# Team18_V1.net
KiCad netlist of a schematic drawn in EAGLE
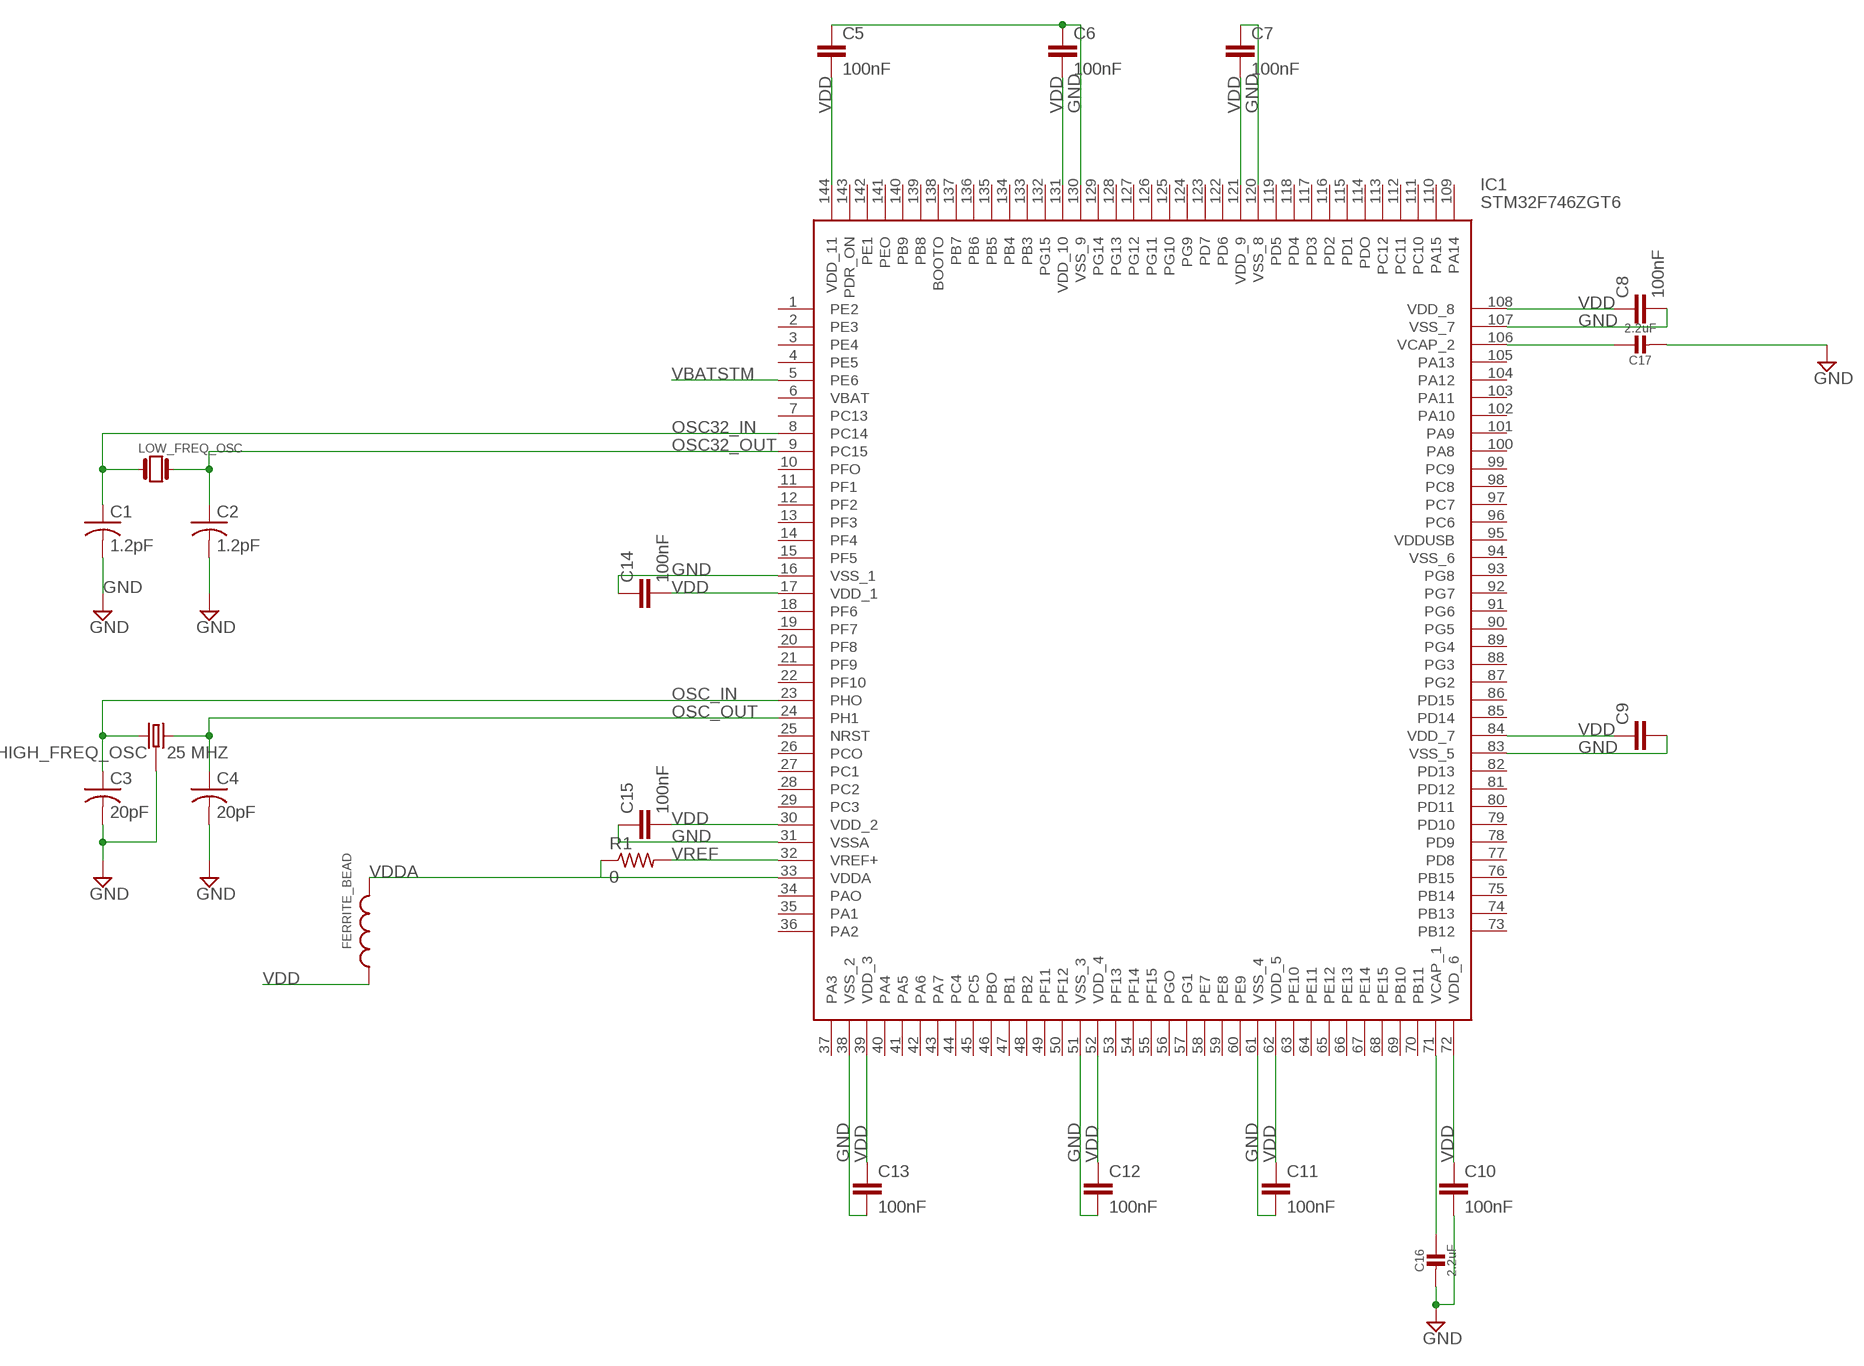
[diagram p0: schematic, sheet 1, part 1 of 2]
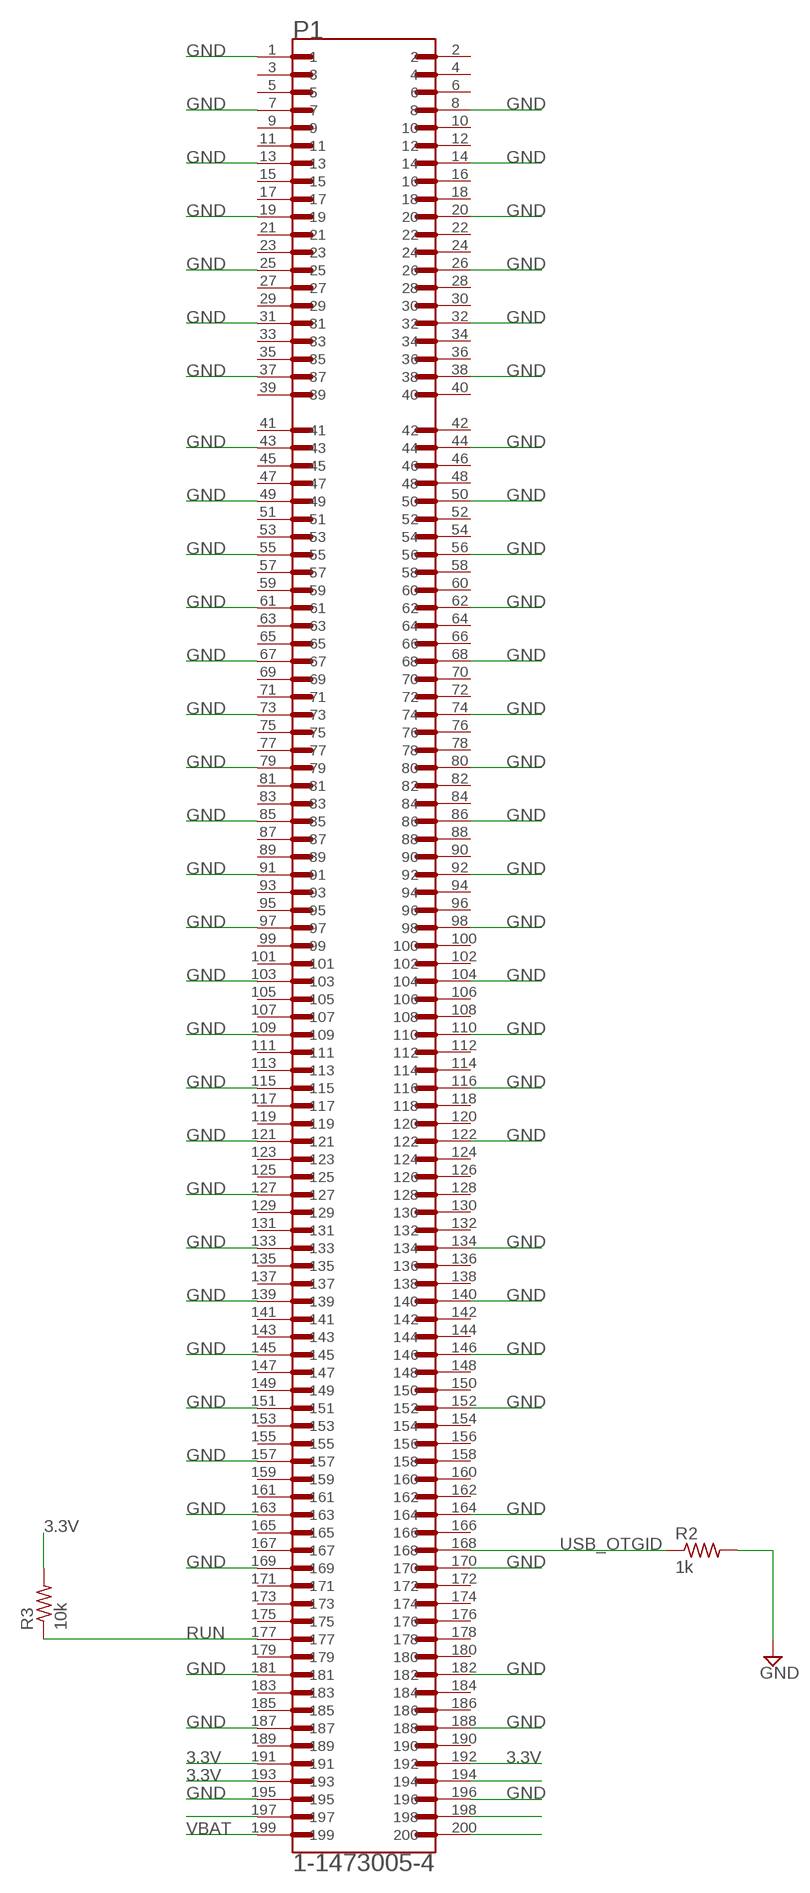
[diagram p1: schematic, sheet 1, part 2 of 2]

(export (version "E")
  (design (tool "Eeschema 10.0.6"))
  (components
    (comp (ref "C1")
      (value "1.2pF")
      (footprint "eagle-import:C0805")
      (libsource (lib "eagle-import") (part "C-USC0805"))
    )
    (comp (ref "C2")
      (value "1.2pF")
      (footprint "eagle-import:C0805")
      (libsource (lib "eagle-import") (part "C-USC0805"))
    )
    (comp (ref "C3")
      (value "20pF")
      (footprint "eagle-import:C0805")
      (libsource (lib "eagle-import") (part "C-USC0805"))
    )
    (comp (ref "C4")
      (value "20pF")
      (footprint "eagle-import:C0805")
      (libsource (lib "eagle-import") (part "C-USC0805"))
    )
    (comp (ref "C5")
      (value "100nF")
      (footprint "eagle-import:C0805")
      (libsource (lib "eagle-import") (part "C-EUC0805"))
    )
    (comp (ref "C6")
      (value "100nF")
      (footprint "eagle-import:C0805")
      (libsource (lib "eagle-import") (part "C-EUC0805"))
    )
    (comp (ref "C7")
      (value "100nF")
      (footprint "eagle-import:C0805")
      (libsource (lib "eagle-import") (part "C-EUC0805"))
    )
    (comp (ref "C8")
      (value "100nF")
      (footprint "eagle-import:C0805")
      (libsource (lib "eagle-import") (part "C-EUC0805"))
    )
    (comp (ref "C9")
      (value "C-EUC0805")
      (footprint "eagle-import:C0805")
      (libsource (lib "eagle-import") (part "C-EUC0805"))
    )
    (comp (ref "C10")
      (value "100nF")
      (footprint "eagle-import:C0805")
      (libsource (lib "eagle-import") (part "C-EUC0805"))
    )
    (comp (ref "C11")
      (value "100nF")
      (footprint "eagle-import:C0805")
      (libsource (lib "eagle-import") (part "C-EUC0805"))
    )
    (comp (ref "C12")
      (value "100nF")
      (footprint "eagle-import:C0805")
      (libsource (lib "eagle-import") (part "C-EUC0805"))
    )
    (comp (ref "C13")
      (value "100nF")
      (footprint "eagle-import:C0805")
      (libsource (lib "eagle-import") (part "C-EUC0805"))
    )
    (comp (ref "C14")
      (value "100nF")
      (footprint "eagle-import:C0805")
      (libsource (lib "eagle-import") (part "C-EUC0805"))
    )
    (comp (ref "C15")
      (value "100nF")
      (footprint "eagle-import:C0805")
      (libsource (lib "eagle-import") (part "C-EUC0805"))
    )
    (comp (ref "C16")
      (value "2.2uF")
      (footprint "eagle-import:0805-NO")
      (libsource (lib "eagle-import") (part "CAP_CERAMIC0805-NOOUTLINE"))
    )
    (comp (ref "C17")
      (value "2.2uF")
      (footprint "eagle-import:0805-NO")
      (libsource (lib "eagle-import") (part "CAP_CERAMIC0805-NOOUTLINE"))
    )
    (comp (ref "FERRITE_BEAD")
      (value "WE-CBA_0805_782853112_HC")
      (footprint "eagle-import:WE-CBA_0805(W=4)")
      (libsource (lib "eagle-import") (part "WE-CBA_0805_HC_782853112"))
    )
    (comp (ref "HIGH_FREQ_OSC")
      (value "25 MHZ")
      (footprint "eagle-import:CRYSTAL-SMD-3.2X2.5MM")
      (libsource (lib "eagle-import") (part "CRYSTAL-26MHZSMD-3.2X2.5"))
    )
    (comp (ref "IC1")
      (value "STM32F746ZGT6")
      (footprint "eagle-import:QFP50P2200X2200X160-144N")
      (fields
        (field (name "MOUSER_PART_NUMBER") "511-STM32F746ZGT6")
        (field (name "RS_PART_NUMBER") "8820290")
      )
      (libsource (lib "eagle-import") (part "STM32F746ZGT6"))
    )
    (comp (ref "LOW_FREQ_OSC")
      (value "GENERIC-CRYSTAL_FC135")
      (footprint "eagle-import:FC135")
      (libsource (lib "eagle-import") (part "GENERIC-CRYSTAL_FC135"))
    )
    (comp (ref "P1")
      (value "1-1473005-4")
      (footprint "eagle-import:TE_1-1473005-4")
      (fields (field (name "MF") "TE Connectivity"))
      (libsource (lib "eagle-import") (part "1-1473005-4"))
    )
    (comp (ref "R1")
      (value "0")
      (footprint "eagle-import:R0805")
      (libsource (lib "eagle-import") (part "R-US_R0805"))
    )
    (comp (ref "R2")
      (value "1k")
      (footprint "eagle-import:R0805")
      (libsource (lib "eagle-import") (part "R-US_R0805"))
    )
    (comp (ref "R3")
      (value "10k")
      (footprint "eagle-import:R0805")
      (libsource (lib "eagle-import") (part "R-US_R0805"))
    )
  )
  (nets
    (net (code "1") (name "/3.3V") (class "Default")
      (node (ref "P1") (pin "191") (pinfunction "191_191") (pintype "passive"))
      (node (ref "P1") (pin "192") (pinfunction "192_192") (pintype "passive"))
      (node (ref "P1") (pin "193") (pinfunction "193_193") (pintype "passive"))
      (node (ref "P1") (pin "194") (pinfunction "194_194") (pintype "passive"))
      (node (ref "R3") (pin "2") (pinfunction "2_2") (pintype "passive"))
    )
    (net (code "2") (name "/OSC32_IN") (class "Default")
      (node (ref "C1") (pin "1") (pinfunction "1_1") (pintype "passive"))
      (node (ref "IC1") (pin "8") (pinfunction "PC14_8") (pintype "bidirectional"))
      (node (ref "LOW_FREQ_OSC") (pin "X1") (pinfunction "1_X1") (pintype "passive"))
    )
    (net (code "3") (name "/OSC32_OUT") (class "Default")
      (node (ref "C2") (pin "1") (pinfunction "1_1") (pintype "passive"))
      (node (ref "IC1") (pin "9") (pinfunction "PC15_9") (pintype "bidirectional"))
      (node (ref "LOW_FREQ_OSC") (pin "X2") (pinfunction "2_X2") (pintype "passive"))
    )
    (net (code "4") (name "/OSC_IN") (class "Default")
      (node (ref "C3") (pin "1") (pinfunction "1_1") (pintype "passive"))
      (node (ref "HIGH_FREQ_OSC") (pin "1") (pinfunction "1_1") (pintype "passive"))
      (node (ref "IC1") (pin "23") (pinfunction "PHO_23") (pintype "bidirectional"))
    )
    (net (code "5") (name "/OSC_OUT") (class "Default")
      (node (ref "C4") (pin "1") (pinfunction "1_1") (pintype "passive"))
      (node (ref "HIGH_FREQ_OSC") (pin "3") (pinfunction "2_3") (pintype "passive"))
      (node (ref "IC1") (pin "24") (pinfunction "PH1_24") (pintype "bidirectional"))
    )
    (net (code "6") (name "/RUN") (class "Default")
      (node (ref "P1") (pin "177") (pinfunction "177_177") (pintype "passive"))
      (node (ref "R3") (pin "1") (pinfunction "1_1") (pintype "passive"))
    )
    (net (code "7") (name "/USB_OTGID") (class "Default")
      (node (ref "P1") (pin "168") (pinfunction "168_168") (pintype "passive"))
      (node (ref "R2") (pin "1") (pinfunction "1_1") (pintype "passive"))
    )
    (net (code "8") (name "/VBAT") (class "Default")
      (node (ref "P1") (pin "197") (pinfunction "197_197") (pintype "passive"))
      (node (ref "P1") (pin "198") (pinfunction "198_198") (pintype "passive"))
      (node (ref "P1") (pin "199") (pinfunction "199_199") (pintype "passive"))
      (node (ref "P1") (pin "200") (pinfunction "200_200") (pintype "passive"))
    )
    (net (code "9") (name "/VBATSTM") (class "Default")
      (node (ref "IC1") (pin "5") (pinfunction "PE6_5") (pintype "bidirectional"))
    )
    (net (code "10") (name "/VDD") (class "Default")
      (node (ref "C10") (pin "1") (pinfunction "1_1") (pintype "passive"))
      (node (ref "C11") (pin "1") (pinfunction "1_1") (pintype "passive"))
      (node (ref "C12") (pin "1") (pinfunction "1_1") (pintype "passive"))
      (node (ref "C13") (pin "1") (pinfunction "1_1") (pintype "passive"))
      (node (ref "C14") (pin "2") (pinfunction "2_2") (pintype "passive"))
      (node (ref "C15") (pin "2") (pinfunction "2_2") (pintype "passive"))
      (node (ref "C5") (pin "2") (pinfunction "2_2") (pintype "passive"))
      (node (ref "C6") (pin "2") (pinfunction "2_2") (pintype "passive"))
      (node (ref "C7") (pin "2") (pinfunction "2_2") (pintype "passive"))
      (node (ref "C8") (pin "1") (pinfunction "1_1") (pintype "passive"))
      (node (ref "C9") (pin "1") (pinfunction "1_1") (pintype "passive"))
      (node (ref "FERRITE_BEAD") (pin "1") (pinfunction "1_1") (pintype "passive"))
      (node (ref "IC1") (pin "108") (pinfunction "VDD_8_108") (pintype "power_in"))
      (node (ref "IC1") (pin "121") (pinfunction "VDD_9_121") (pintype "power_in"))
      (node (ref "IC1") (pin "131") (pinfunction "VDD_10_131") (pintype "power_in"))
      (node (ref "IC1") (pin "144") (pinfunction "VDD_11_144") (pintype "power_in"))
      (node (ref "IC1") (pin "17") (pinfunction "VDD_1_17") (pintype "power_in"))
      (node (ref "IC1") (pin "30") (pinfunction "VDD_2_30") (pintype "power_in"))
      (node (ref "IC1") (pin "39") (pinfunction "VDD_3_39") (pintype "power_in"))
      (node (ref "IC1") (pin "52") (pinfunction "VDD_4_52") (pintype "power_in"))
      (node (ref "IC1") (pin "62") (pinfunction "VDD_5_62") (pintype "power_in"))
      (node (ref "IC1") (pin "72") (pinfunction "VDD_6_72") (pintype "power_in"))
      (node (ref "IC1") (pin "84") (pinfunction "VDD_7_84") (pintype "power_in"))
    )
    (net (code "11") (name "/VDDA") (class "Default")
      (node (ref "FERRITE_BEAD") (pin "2") (pinfunction "2_2") (pintype "passive"))
      (node (ref "IC1") (pin "33") (pinfunction "VDDA_33") (pintype "power_in"))
      (node (ref "R1") (pin "1") (pinfunction "1_1") (pintype "passive"))
    )
    (net (code "12") (name "/VDDUSB") (class "Default")
      (node (ref "IC1") (pin "95") (pinfunction "VDDUSB_95") (pintype "power_in"))
    )
    (net (code "13") (name "/VREF") (class "Default")
      (node (ref "IC1") (pin "32") (pinfunction "VREF+_32") (pintype "input"))
      (node (ref "R1") (pin "2") (pinfunction "2_2") (pintype "passive"))
    )
    (net (code "14") (name "/VSS_6") (class "Default")
      (node (ref "IC1") (pin "94") (pinfunction "VSS_6_94") (pintype "power_in"))
    )
    (net (code "15") (name "GND") (class "Default")
      (node (ref "C1") (pin "2") (pinfunction "2_2") (pintype "passive"))
      (node (ref "C10") (pin "2") (pinfunction "2_2") (pintype "passive"))
      (node (ref "C11") (pin "2") (pinfunction "2_2") (pintype "passive"))
      (node (ref "C12") (pin "2") (pinfunction "2_2") (pintype "passive"))
      (node (ref "C13") (pin "2") (pinfunction "2_2") (pintype "passive"))
      (node (ref "C14") (pin "1") (pinfunction "1_1") (pintype "passive"))
      (node (ref "C15") (pin "1") (pinfunction "1_1") (pintype "passive"))
      (node (ref "C16") (pin "2") (pinfunction "2_2") (pintype "passive"))
      (node (ref "C17") (pin "2") (pinfunction "2_2") (pintype "passive"))
      (node (ref "C2") (pin "2") (pinfunction "2_2") (pintype "passive"))
      (node (ref "C3") (pin "2") (pinfunction "2_2") (pintype "passive"))
      (node (ref "C4") (pin "2") (pinfunction "2_2") (pintype "passive"))
      (node (ref "C5") (pin "1") (pinfunction "1_1") (pintype "passive"))
      (node (ref "C6") (pin "1") (pinfunction "1_1") (pintype "passive"))
      (node (ref "C7") (pin "1") (pinfunction "1_1") (pintype "passive"))
      (node (ref "C8") (pin "2") (pinfunction "2_2") (pintype "passive"))
      (node (ref "C9") (pin "2") (pinfunction "2_2") (pintype "passive"))
      (node (ref "HIGH_FREQ_OSC") (pin "2") (pinfunction "3_2") (pintype "passive"))
      (node (ref "HIGH_FREQ_OSC") (pin "4") (pinfunction "3_4") (pintype "passive"))
      (node (ref "IC1") (pin "107") (pinfunction "VSS_7_107") (pintype "power_in"))
      (node (ref "IC1") (pin "120") (pinfunction "VSS_8_120") (pintype "power_in"))
      (node (ref "IC1") (pin "130") (pinfunction "VSS_9_130") (pintype "power_in"))
      (node (ref "IC1") (pin "16") (pinfunction "VSS_1_16") (pintype "power_in"))
      (node (ref "IC1") (pin "31") (pinfunction "VSSA_31") (pintype "power_in"))
      (node (ref "IC1") (pin "38") (pinfunction "VSS_2_38") (pintype "power_in"))
      (node (ref "IC1") (pin "51") (pinfunction "VSS_3_51") (pintype "power_in"))
      (node (ref "IC1") (pin "61") (pinfunction "VSS_4_61") (pintype "power_in"))
      (node (ref "IC1") (pin "83") (pinfunction "VSS_5_83") (pintype "power_in"))
      (node (ref "P1") (pin "1") (pinfunction "1_1") (pintype "passive"))
      (node (ref "P1") (pin "103") (pinfunction "103_103") (pintype "passive"))
      (node (ref "P1") (pin "104") (pinfunction "104_104") (pintype "passive"))
      (node (ref "P1") (pin "109") (pinfunction "109_109") (pintype "passive"))
      (node (ref "P1") (pin "110") (pinfunction "110_110") (pintype "passive"))
      (node (ref "P1") (pin "115") (pinfunction "115_115") (pintype "passive"))
      (node (ref "P1") (pin "116") (pinfunction "116_116") (pintype "passive"))
      (node (ref "P1") (pin "121") (pinfunction "121_121") (pintype "passive"))
      (node (ref "P1") (pin "122") (pinfunction "122_122") (pintype "passive"))
      (node (ref "P1") (pin "127") (pinfunction "127_127") (pintype "passive"))
      (node (ref "P1") (pin "13") (pinfunction "13_13") (pintype "passive"))
      (node (ref "P1") (pin "133") (pinfunction "133_133") (pintype "passive"))
      (node (ref "P1") (pin "134") (pinfunction "134_134") (pintype "passive"))
      (node (ref "P1") (pin "139") (pinfunction "139_139") (pintype "passive"))
      (node (ref "P1") (pin "14") (pinfunction "14_14") (pintype "passive"))
      (node (ref "P1") (pin "140") (pinfunction "140_140") (pintype "passive"))
      (node (ref "P1") (pin "145") (pinfunction "145_145") (pintype "passive"))
      (node (ref "P1") (pin "146") (pinfunction "146_146") (pintype "passive"))
      (node (ref "P1") (pin "151") (pinfunction "151_151") (pintype "passive"))
      (node (ref "P1") (pin "152") (pinfunction "152_152") (pintype "passive"))
      (node (ref "P1") (pin "157") (pinfunction "157_157") (pintype "passive"))
      (node (ref "P1") (pin "163") (pinfunction "163_163") (pintype "passive"))
      (node (ref "P1") (pin "164") (pinfunction "164_164") (pintype "passive"))
      (node (ref "P1") (pin "169") (pinfunction "169_169") (pintype "passive"))
      (node (ref "P1") (pin "170") (pinfunction "170_170") (pintype "passive"))
      (node (ref "P1") (pin "181") (pinfunction "181_181") (pintype "passive"))
      (node (ref "P1") (pin "182") (pinfunction "182_182") (pintype "passive"))
      (node (ref "P1") (pin "187") (pinfunction "187_187") (pintype "passive"))
      (node (ref "P1") (pin "188") (pinfunction "188_188") (pintype "passive"))
      (node (ref "P1") (pin "19") (pinfunction "19_19") (pintype "passive"))
      (node (ref "P1") (pin "195") (pinfunction "195_195") (pintype "passive"))
      (node (ref "P1") (pin "196") (pinfunction "196_196") (pintype "passive"))
      (node (ref "P1") (pin "20") (pinfunction "20_20") (pintype "passive"))
      (node (ref "P1") (pin "25") (pinfunction "25_25") (pintype "passive"))
      (node (ref "P1") (pin "26") (pinfunction "26_26") (pintype "passive"))
      (node (ref "P1") (pin "31") (pinfunction "31_31") (pintype "passive"))
      (node (ref "P1") (pin "32") (pinfunction "32_32") (pintype "passive"))
      (node (ref "P1") (pin "37") (pinfunction "37_37") (pintype "passive"))
      (node (ref "P1") (pin "38") (pinfunction "38_38") (pintype "passive"))
      (node (ref "P1") (pin "43") (pinfunction "43_43") (pintype "passive"))
      (node (ref "P1") (pin "44") (pinfunction "44_44") (pintype "passive"))
      (node (ref "P1") (pin "49") (pinfunction "49_49") (pintype "passive"))
      (node (ref "P1") (pin "50") (pinfunction "50_50") (pintype "passive"))
      (node (ref "P1") (pin "55") (pinfunction "55_55") (pintype "passive"))
      (node (ref "P1") (pin "56") (pinfunction "56_56") (pintype "passive"))
      (node (ref "P1") (pin "61") (pinfunction "61_61") (pintype "passive"))
      (node (ref "P1") (pin "62") (pinfunction "62_62") (pintype "passive"))
      (node (ref "P1") (pin "67") (pinfunction "67_67") (pintype "passive"))
      (node (ref "P1") (pin "68") (pinfunction "68_68") (pintype "passive"))
      (node (ref "P1") (pin "7") (pinfunction "7_7") (pintype "passive"))
      (node (ref "P1") (pin "73") (pinfunction "73_73") (pintype "passive"))
      (node (ref "P1") (pin "74") (pinfunction "74_74") (pintype "passive"))
      (node (ref "P1") (pin "79") (pinfunction "79_79") (pintype "passive"))
      (node (ref "P1") (pin "8") (pinfunction "8_8") (pintype "passive"))
      (node (ref "P1") (pin "80") (pinfunction "80_80") (pintype "passive"))
      (node (ref "P1") (pin "85") (pinfunction "85_85") (pintype "passive"))
      (node (ref "P1") (pin "86") (pinfunction "86_86") (pintype "passive"))
      (node (ref "P1") (pin "91") (pinfunction "91_91") (pintype "passive"))
      (node (ref "P1") (pin "92") (pinfunction "92_92") (pintype "passive"))
      (node (ref "P1") (pin "97") (pinfunction "97_97") (pintype "passive"))
      (node (ref "P1") (pin "98") (pinfunction "98_98") (pintype "passive"))
      (node (ref "R2") (pin "2") (pinfunction "2_2") (pintype "passive"))
    )
    (net (code "16") (name "Net-(IC1-VCAP_1)") (class "Default")
      (node (ref "C16") (pin "1") (pinfunction "1_1") (pintype "passive"))
      (node (ref "IC1") (pin "71") (pinfunction "VCAP_1_71") (pintype "bidirectional"))
    )
    (net (code "17") (name "Net-(IC1-VCAP_2)") (class "Default")
      (node (ref "C17") (pin "1") (pinfunction "1_1") (pintype "passive"))
      (node (ref "IC1") (pin "106") (pinfunction "VCAP_2_106") (pintype "bidirectional"))
    )
    (net (code "18") (name "unconnected-(IC1-BOOTO-Pad138)") (class "Default")
      (node (ref "IC1") (pin "138") (pinfunction "BOOTO_138") (pintype "bidirectional"))
    )
    (net (code "19") (name "unconnected-(IC1-NRST-Pad25)") (class "Default")
      (node (ref "IC1") (pin "25") (pinfunction "NRST_25") (pintype "input"))
    )
    (net (code "20") (name "unconnected-(IC1-PA1-Pad35)") (class "Default")
      (node (ref "IC1") (pin "35") (pinfunction "PA1_35") (pintype "bidirectional"))
    )
    (net (code "21") (name "unconnected-(IC1-PA2-Pad36)") (class "Default")
      (node (ref "IC1") (pin "36") (pinfunction "PA2_36") (pintype "bidirectional"))
    )
    (net (code "22") (name "unconnected-(IC1-PA3-Pad37)") (class "Default")
      (node (ref "IC1") (pin "37") (pinfunction "PA3_37") (pintype "bidirectional"))
    )
    (net (code "23") (name "unconnected-(IC1-PA4-Pad40)") (class "Default")
      (node (ref "IC1") (pin "40") (pinfunction "PA4_40") (pintype "bidirectional"))
    )
    (net (code "24") (name "unconnected-(IC1-PA5-Pad41)") (class "Default")
      (node (ref "IC1") (pin "41") (pinfunction "PA5_41") (pintype "bidirectional"))
    )
    (net (code "25") (name "unconnected-(IC1-PA6-Pad42)") (class "Default")
      (node (ref "IC1") (pin "42") (pinfunction "PA6_42") (pintype "bidirectional"))
    )
    (net (code "26") (name "unconnected-(IC1-PA7-Pad43)") (class "Default")
      (node (ref "IC1") (pin "43") (pinfunction "PA7_43") (pintype "bidirectional"))
    )
    (net (code "27") (name "unconnected-(IC1-PA8-Pad100)") (class "Default")
      (node (ref "IC1") (pin "100") (pinfunction "PA8_100") (pintype "bidirectional"))
    )
    (net (code "28") (name "unconnected-(IC1-PA9-Pad101)") (class "Default")
      (node (ref "IC1") (pin "101") (pinfunction "PA9_101") (pintype "bidirectional"))
    )
    (net (code "29") (name "unconnected-(IC1-PA10-Pad102)") (class "Default")
      (node (ref "IC1") (pin "102") (pinfunction "PA10_102") (pintype "bidirectional"))
    )
    (net (code "30") (name "unconnected-(IC1-PA11-Pad103)") (class "Default")
      (node (ref "IC1") (pin "103") (pinfunction "PA11_103") (pintype "bidirectional"))
    )
    (net (code "31") (name "unconnected-(IC1-PA12-Pad104)") (class "Default")
      (node (ref "IC1") (pin "104") (pinfunction "PA12_104") (pintype "bidirectional"))
    )
    (net (code "32") (name "unconnected-(IC1-PA13-Pad105)") (class "Default")
      (node (ref "IC1") (pin "105") (pinfunction "PA13_105") (pintype "bidirectional"))
    )
    (net (code "33") (name "unconnected-(IC1-PA14-Pad109)") (class "Default")
      (node (ref "IC1") (pin "109") (pinfunction "PA14_109") (pintype "bidirectional"))
    )
    (net (code "34") (name "unconnected-(IC1-PA15-Pad110)") (class "Default")
      (node (ref "IC1") (pin "110") (pinfunction "PA15_110") (pintype "bidirectional"))
    )
    (net (code "35") (name "unconnected-(IC1-PAO-Pad34)") (class "Default")
      (node (ref "IC1") (pin "34") (pinfunction "PAO_34") (pintype "bidirectional"))
    )
    (net (code "36") (name "unconnected-(IC1-PB1-Pad47)") (class "Default")
      (node (ref "IC1") (pin "47") (pinfunction "PB1_47") (pintype "bidirectional"))
    )
    (net (code "37") (name "unconnected-(IC1-PB2-Pad48)") (class "Default")
      (node (ref "IC1") (pin "48") (pinfunction "PB2_48") (pintype "bidirectional"))
    )
    (net (code "38") (name "unconnected-(IC1-PB3-Pad133)") (class "Default")
      (node (ref "IC1") (pin "133") (pinfunction "PB3_133") (pintype "bidirectional"))
    )
    (net (code "39") (name "unconnected-(IC1-PB4-Pad134)") (class "Default")
      (node (ref "IC1") (pin "134") (pinfunction "PB4_134") (pintype "bidirectional"))
    )
    (net (code "40") (name "unconnected-(IC1-PB5-Pad135)") (class "Default")
      (node (ref "IC1") (pin "135") (pinfunction "PB5_135") (pintype "bidirectional"))
    )
    (net (code "41") (name "unconnected-(IC1-PB6-Pad136)") (class "Default")
      (node (ref "IC1") (pin "136") (pinfunction "PB6_136") (pintype "bidirectional"))
    )
    (net (code "42") (name "unconnected-(IC1-PB7-Pad137)") (class "Default")
      (node (ref "IC1") (pin "137") (pinfunction "PB7_137") (pintype "bidirectional"))
    )
    (net (code "43") (name "unconnected-(IC1-PB8-Pad139)") (class "Default")
      (node (ref "IC1") (pin "139") (pinfunction "PB8_139") (pintype "bidirectional"))
    )
    (net (code "44") (name "unconnected-(IC1-PB9-Pad140)") (class "Default")
      (node (ref "IC1") (pin "140") (pinfunction "PB9_140") (pintype "bidirectional"))
    )
    (net (code "45") (name "unconnected-(IC1-PB10-Pad69)") (class "Default")
      (node (ref "IC1") (pin "69") (pinfunction "PB10_69") (pintype "bidirectional"))
    )
    (net (code "46") (name "unconnected-(IC1-PB11-Pad70)") (class "Default")
      (node (ref "IC1") (pin "70") (pinfunction "PB11_70") (pintype "bidirectional"))
    )
    (net (code "47") (name "unconnected-(IC1-PB12-Pad73)") (class "Default")
      (node (ref "IC1") (pin "73") (pinfunction "PB12_73") (pintype "bidirectional"))
    )
    (net (code "48") (name "unconnected-(IC1-PB13-Pad74)") (class "Default")
      (node (ref "IC1") (pin "74") (pinfunction "PB13_74") (pintype "bidirectional"))
    )
    (net (code "49") (name "unconnected-(IC1-PB14-Pad75)") (class "Default")
      (node (ref "IC1") (pin "75") (pinfunction "PB14_75") (pintype "bidirectional"))
    )
    (net (code "50") (name "unconnected-(IC1-PB15-Pad76)") (class "Default")
      (node (ref "IC1") (pin "76") (pinfunction "PB15_76") (pintype "bidirectional"))
    )
    (net (code "51") (name "unconnected-(IC1-PBO-Pad46)") (class "Default")
      (node (ref "IC1") (pin "46") (pinfunction "PBO_46") (pintype "bidirectional"))
    )
    (net (code "52") (name "unconnected-(IC1-PC1-Pad27)") (class "Default")
      (node (ref "IC1") (pin "27") (pinfunction "PC1_27") (pintype "bidirectional"))
    )
    (net (code "53") (name "unconnected-(IC1-PC2-Pad28)") (class "Default")
      (node (ref "IC1") (pin "28") (pinfunction "PC2_28") (pintype "bidirectional"))
    )
    (net (code "54") (name "unconnected-(IC1-PC3-Pad29)") (class "Default")
      (node (ref "IC1") (pin "29") (pinfunction "PC3_29") (pintype "bidirectional"))
    )
    (net (code "55") (name "unconnected-(IC1-PC4-Pad44)") (class "Default")
      (node (ref "IC1") (pin "44") (pinfunction "PC4_44") (pintype "bidirectional"))
    )
    (net (code "56") (name "unconnected-(IC1-PC5-Pad45)") (class "Default")
      (node (ref "IC1") (pin "45") (pinfunction "PC5_45") (pintype "bidirectional"))
    )
    (net (code "57") (name "unconnected-(IC1-PC6-Pad96)") (class "Default")
      (node (ref "IC1") (pin "96") (pinfunction "PC6_96") (pintype "bidirectional"))
    )
    (net (code "58") (name "unconnected-(IC1-PC7-Pad97)") (class "Default")
      (node (ref "IC1") (pin "97") (pinfunction "PC7_97") (pintype "bidirectional"))
    )
    (net (code "59") (name "unconnected-(IC1-PC8-Pad98)") (class "Default")
      (node (ref "IC1") (pin "98") (pinfunction "PC8_98") (pintype "bidirectional"))
    )
    (net (code "60") (name "unconnected-(IC1-PC9-Pad99)") (class "Default")
      (node (ref "IC1") (pin "99") (pinfunction "PC9_99") (pintype "bidirectional"))
    )
    (net (code "61") (name "unconnected-(IC1-PC10-Pad111)") (class "Default")
      (node (ref "IC1") (pin "111") (pinfunction "PC10_111") (pintype "bidirectional"))
    )
    (net (code "62") (name "unconnected-(IC1-PC11-Pad112)") (class "Default")
      (node (ref "IC1") (pin "112") (pinfunction "PC11_112") (pintype "bidirectional"))
    )
    (net (code "63") (name "unconnected-(IC1-PC12-Pad113)") (class "Default")
      (node (ref "IC1") (pin "113") (pinfunction "PC12_113") (pintype "bidirectional"))
    )
    (net (code "64") (name "unconnected-(IC1-PC13-Pad7)") (class "Default")
      (node (ref "IC1") (pin "7") (pinfunction "PC13_7") (pintype "bidirectional"))
    )
    (net (code "65") (name "unconnected-(IC1-PCO-Pad26)") (class "Default")
      (node (ref "IC1") (pin "26") (pinfunction "PCO_26") (pintype "bidirectional"))
    )
    (net (code "66") (name "unconnected-(IC1-PD1-Pad115)") (class "Default")
      (node (ref "IC1") (pin "115") (pinfunction "PD1_115") (pintype "bidirectional"))
    )
    (net (code "67") (name "unconnected-(IC1-PD2-Pad116)") (class "Default")
      (node (ref "IC1") (pin "116") (pinfunction "PD2_116") (pintype "bidirectional"))
    )
    (net (code "68") (name "unconnected-(IC1-PD3-Pad117)") (class "Default")
      (node (ref "IC1") (pin "117") (pinfunction "PD3_117") (pintype "bidirectional"))
    )
    (net (code "69") (name "unconnected-(IC1-PD4-Pad118)") (class "Default")
      (node (ref "IC1") (pin "118") (pinfunction "PD4_118") (pintype "bidirectional"))
    )
    (net (code "70") (name "unconnected-(IC1-PD5-Pad119)") (class "Default")
      (node (ref "IC1") (pin "119") (pinfunction "PD5_119") (pintype "bidirectional"))
    )
    (net (code "71") (name "unconnected-(IC1-PD6-Pad122)") (class "Default")
      (node (ref "IC1") (pin "122") (pinfunction "PD6_122") (pintype "bidirectional"))
    )
    (net (code "72") (name "unconnected-(IC1-PD7-Pad123)") (class "Default")
      (node (ref "IC1") (pin "123") (pinfunction "PD7_123") (pintype "bidirectional"))
    )
    (net (code "73") (name "unconnected-(IC1-PD8-Pad77)") (class "Default")
      (node (ref "IC1") (pin "77") (pinfunction "PD8_77") (pintype "bidirectional"))
    )
    (net (code "74") (name "unconnected-(IC1-PD9-Pad78)") (class "Default")
      (node (ref "IC1") (pin "78") (pinfunction "PD9_78") (pintype "bidirectional"))
    )
    (net (code "75") (name "unconnected-(IC1-PD10-Pad79)") (class "Default")
      (node (ref "IC1") (pin "79") (pinfunction "PD10_79") (pintype "bidirectional"))
    )
    (net (code "76") (name "unconnected-(IC1-PD11-Pad80)") (class "Default")
      (node (ref "IC1") (pin "80") (pinfunction "PD11_80") (pintype "bidirectional"))
    )
    (net (code "77") (name "unconnected-(IC1-PD12-Pad81)") (class "Default")
      (node (ref "IC1") (pin "81") (pinfunction "PD12_81") (pintype "bidirectional"))
    )
    (net (code "78") (name "unconnected-(IC1-PD13-Pad82)") (class "Default")
      (node (ref "IC1") (pin "82") (pinfunction "PD13_82") (pintype "bidirectional"))
    )
    (net (code "79") (name "unconnected-(IC1-PD14-Pad85)") (class "Default")
      (node (ref "IC1") (pin "85") (pinfunction "PD14_85") (pintype "bidirectional"))
    )
    (net (code "80") (name "unconnected-(IC1-PD15-Pad86)") (class "Default")
      (node (ref "IC1") (pin "86") (pinfunction "PD15_86") (pintype "bidirectional"))
    )
    (net (code "81") (name "unconnected-(IC1-PDO-Pad114)") (class "Default")
      (node (ref "IC1") (pin "114") (pinfunction "PDO_114") (pintype "bidirectional"))
    )
    (net (code "82") (name "unconnected-(IC1-PDR_ON-Pad143)") (class "Default")
      (node (ref "IC1") (pin "143") (pinfunction "PDR_ON_143") (pintype "bidirectional"))
    )
    (net (code "83") (name "unconnected-(IC1-PE1-Pad142)") (class "Default")
      (node (ref "IC1") (pin "142") (pinfunction "PE1_142") (pintype "bidirectional"))
    )
    (net (code "84") (name "unconnected-(IC1-PE2-Pad1)") (class "Default")
      (node (ref "IC1") (pin "1") (pinfunction "PE2_1") (pintype "bidirectional"))
    )
    (net (code "85") (name "unconnected-(IC1-PE3-Pad2)") (class "Default")
      (node (ref "IC1") (pin "2") (pinfunction "PE3_2") (pintype "bidirectional"))
    )
    (net (code "86") (name "unconnected-(IC1-PE4-Pad3)") (class "Default")
      (node (ref "IC1") (pin "3") (pinfunction "PE4_3") (pintype "bidirectional"))
    )
    (net (code "87") (name "unconnected-(IC1-PE5-Pad4)") (class "Default")
      (node (ref "IC1") (pin "4") (pinfunction "PE5_4") (pintype "bidirectional"))
    )
    (net (code "88") (name "unconnected-(IC1-PE7-Pad58)") (class "Default")
      (node (ref "IC1") (pin "58") (pinfunction "PE7_58") (pintype "bidirectional"))
    )
    (net (code "89") (name "unconnected-(IC1-PE8-Pad59)") (class "Default")
      (node (ref "IC1") (pin "59") (pinfunction "PE8_59") (pintype "bidirectional"))
    )
    (net (code "90") (name "unconnected-(IC1-PE9-Pad60)") (class "Default")
      (node (ref "IC1") (pin "60") (pinfunction "PE9_60") (pintype "bidirectional"))
    )
    (net (code "91") (name "unconnected-(IC1-PE10-Pad63)") (class "Default")
      (node (ref "IC1") (pin "63") (pinfunction "PE10_63") (pintype "bidirectional"))
    )
    (net (code "92") (name "unconnected-(IC1-PE11-Pad64)") (class "Default")
      (node (ref "IC1") (pin "64") (pinfunction "PE11_64") (pintype "bidirectional"))
    )
    (net (code "93") (name "unconnected-(IC1-PE12-Pad65)") (class "Default")
      (node (ref "IC1") (pin "65") (pinfunction "PE12_65") (pintype "bidirectional"))
    )
    (net (code "94") (name "unconnected-(IC1-PE13-Pad66)") (class "Default")
      (node (ref "IC1") (pin "66") (pinfunction "PE13_66") (pintype "bidirectional"))
    )
    (net (code "95") (name "unconnected-(IC1-PE14-Pad67)") (class "Default")
      (node (ref "IC1") (pin "67") (pinfunction "PE14_67") (pintype "bidirectional"))
    )
    (net (code "96") (name "unconnected-(IC1-PE15-Pad68)") (class "Default")
      (node (ref "IC1") (pin "68") (pinfunction "PE15_68") (pintype "bidirectional"))
    )
    (net (code "97") (name "unconnected-(IC1-PEO-Pad141)") (class "Default")
      (node (ref "IC1") (pin "141") (pinfunction "PEO_141") (pintype "bidirectional"))
    )
    (net (code "98") (name "unconnected-(IC1-PF1-Pad11)") (class "Default")
      (node (ref "IC1") (pin "11") (pinfunction "PF1_11") (pintype "bidirectional"))
    )
    (net (code "99") (name "unconnected-(IC1-PF2-Pad12)") (class "Default")
      (node (ref "IC1") (pin "12") (pinfunction "PF2_12") (pintype "bidirectional"))
    )
    (net (code "100") (name "unconnected-(IC1-PF3-Pad13)") (class "Default")
      (node (ref "IC1") (pin "13") (pinfunction "PF3_13") (pintype "bidirectional"))
    )
    (net (code "101") (name "unconnected-(IC1-PF4-Pad14)") (class "Default")
      (node (ref "IC1") (pin "14") (pinfunction "PF4_14") (pintype "bidirectional"))
    )
    (net (code "102") (name "unconnected-(IC1-PF5-Pad15)") (class "Default")
      (node (ref "IC1") (pin "15") (pinfunction "PF5_15") (pintype "bidirectional"))
    )
    (net (code "103") (name "unconnected-(IC1-PF6-Pad18)") (class "Default")
      (node (ref "IC1") (pin "18") (pinfunction "PF6_18") (pintype "bidirectional"))
    )
    (net (code "104") (name "unconnected-(IC1-PF7-Pad19)") (class "Default")
      (node (ref "IC1") (pin "19") (pinfunction "PF7_19") (pintype "bidirectional"))
    )
    (net (code "105") (name "unconnected-(IC1-PF8-Pad20)") (class "Default")
      (node (ref "IC1") (pin "20") (pinfunction "PF8_20") (pintype "bidirectional"))
    )
    (net (code "106") (name "unconnected-(IC1-PF9-Pad21)") (class "Default")
      (node (ref "IC1") (pin "21") (pinfunction "PF9_21") (pintype "bidirectional"))
    )
    (net (code "107") (name "unconnected-(IC1-PF10-Pad22)") (class "Default")
      (node (ref "IC1") (pin "22") (pinfunction "PF10_22") (pintype "bidirectional"))
    )
    (net (code "108") (name "unconnected-(IC1-PF11-Pad49)") (class "Default")
      (node (ref "IC1") (pin "49") (pinfunction "PF11_49") (pintype "bidirectional"))
    )
    (net (code "109") (name "unconnected-(IC1-PF12-Pad50)") (class "Default")
      (node (ref "IC1") (pin "50") (pinfunction "PF12_50") (pintype "bidirectional"))
    )
    (net (code "110") (name "unconnected-(IC1-PF13-Pad53)") (class "Default")
      (node (ref "IC1") (pin "53") (pinfunction "PF13_53") (pintype "bidirectional"))
    )
    (net (code "111") (name "unconnected-(IC1-PF14-Pad54)") (class "Default")
      (node (ref "IC1") (pin "54") (pinfunction "PF14_54") (pintype "bidirectional"))
    )
    (net (code "112") (name "unconnected-(IC1-PF15-Pad55)") (class "Default")
      (node (ref "IC1") (pin "55") (pinfunction "PF15_55") (pintype "bidirectional"))
    )
    (net (code "113") (name "unconnected-(IC1-PFO-Pad10)") (class "Default")
      (node (ref "IC1") (pin "10") (pinfunction "PFO_10") (pintype "bidirectional"))
    )
    (net (code "114") (name "unconnected-(IC1-PG1-Pad57)") (class "Default")
      (node (ref "IC1") (pin "57") (pinfunction "PG1_57") (pintype "bidirectional"))
    )
    (net (code "115") (name "unconnected-(IC1-PG2-Pad87)") (class "Default")
      (node (ref "IC1") (pin "87") (pinfunction "PG2_87") (pintype "bidirectional"))
    )
    (net (code "116") (name "unconnected-(IC1-PG3-Pad88)") (class "Default")
      (node (ref "IC1") (pin "88") (pinfunction "PG3_88") (pintype "bidirectional"))
    )
    (net (code "117") (name "unconnected-(IC1-PG4-Pad89)") (class "Default")
      (node (ref "IC1") (pin "89") (pinfunction "PG4_89") (pintype "bidirectional"))
    )
    (net (code "118") (name "unconnected-(IC1-PG5-Pad90)") (class "Default")
      (node (ref "IC1") (pin "90") (pinfunction "PG5_90") (pintype "bidirectional"))
    )
    (net (code "119") (name "unconnected-(IC1-PG6-Pad91)") (class "Default")
      (node (ref "IC1") (pin "91") (pinfunction "PG6_91") (pintype "bidirectional"))
    )
    (net (code "120") (name "unconnected-(IC1-PG7-Pad92)") (class "Default")
      (node (ref "IC1") (pin "92") (pinfunction "PG7_92") (pintype "bidirectional"))
    )
    (net (code "121") (name "unconnected-(IC1-PG8-Pad93)") (class "Default")
      (node (ref "IC1") (pin "93") (pinfunction "PG8_93") (pintype "bidirectional"))
    )
    (net (code "122") (name "unconnected-(IC1-PG9-Pad124)") (class "Default")
      (node (ref "IC1") (pin "124") (pinfunction "PG9_124") (pintype "bidirectional"))
    )
    (net (code "123") (name "unconnected-(IC1-PG10-Pad125)") (class "Default")
      (node (ref "IC1") (pin "125") (pinfunction "PG10_125") (pintype "bidirectional"))
    )
    (net (code "124") (name "unconnected-(IC1-PG11-Pad126)") (class "Default")
      (node (ref "IC1") (pin "126") (pinfunction "PG11_126") (pintype "bidirectional"))
    )
    (net (code "125") (name "unconnected-(IC1-PG12-Pad127)") (class "Default")
      (node (ref "IC1") (pin "127") (pinfunction "PG12_127") (pintype "bidirectional"))
    )
    (net (code "126") (name "unconnected-(IC1-PG13-Pad128)") (class "Default")
      (node (ref "IC1") (pin "128") (pinfunction "PG13_128") (pintype "bidirectional"))
    )
    (net (code "127") (name "unconnected-(IC1-PG14-Pad129)") (class "Default")
      (node (ref "IC1") (pin "129") (pinfunction "PG14_129") (pintype "bidirectional"))
    )
    (net (code "128") (name "unconnected-(IC1-PG15-Pad132)") (class "Default")
      (node (ref "IC1") (pin "132") (pinfunction "PG15_132") (pintype "bidirectional"))
    )
    (net (code "129") (name "unconnected-(IC1-PGO-Pad56)") (class "Default")
      (node (ref "IC1") (pin "56") (pinfunction "PGO_56") (pintype "bidirectional"))
    )
    (net (code "130") (name "unconnected-(IC1-VBAT-Pad6)") (class "Default")
      (node (ref "IC1") (pin "6") (pinfunction "VBAT_6") (pintype "bidirectional"))
    )
    (net (code "131") (name "unconnected-(P1-Pad2)") (class "Default")
      (node (ref "P1") (pin "2") (pinfunction "2_2") (pintype "passive"))
    )
    (net (code "132") (name "unconnected-(P1-Pad3)") (class "Default")
      (node (ref "P1") (pin "3") (pinfunction "3_3") (pintype "passive"))
    )
    (net (code "133") (name "unconnected-(P1-Pad4)") (class "Default")
      (node (ref "P1") (pin "4") (pinfunction "4_4") (pintype "passive"))
    )
    (net (code "134") (name "unconnected-(P1-Pad5)") (class "Default")
      (node (ref "P1") (pin "5") (pinfunction "5_5") (pintype "passive"))
    )
    (net (code "135") (name "unconnected-(P1-Pad6)") (class "Default")
      (node (ref "P1") (pin "6") (pinfunction "6_6") (pintype "passive"))
    )
    (net (code "136") (name "unconnected-(P1-Pad9)") (class "Default")
      (node (ref "P1") (pin "9") (pinfunction "9_9") (pintype "passive"))
    )
    (net (code "137") (name "unconnected-(P1-Pad10)") (class "Default")
      (node (ref "P1") (pin "10") (pinfunction "10_10") (pintype "passive"))
    )
    (net (code "138") (name "unconnected-(P1-Pad11)") (class "Default")
      (node (ref "P1") (pin "11") (pinfunction "11_11") (pintype "passive"))
    )
    (net (code "139") (name "unconnected-(P1-Pad12)") (class "Default")
      (node (ref "P1") (pin "12") (pinfunction "12_12") (pintype "passive"))
    )
    (net (code "140") (name "unconnected-(P1-Pad15)") (class "Default")
      (node (ref "P1") (pin "15") (pinfunction "15_15") (pintype "passive"))
    )
    (net (code "141") (name "unconnected-(P1-Pad16)") (class "Default")
      (node (ref "P1") (pin "16") (pinfunction "16_16") (pintype "passive"))
    )
    (net (code "142") (name "unconnected-(P1-Pad17)") (class "Default")
      (node (ref "P1") (pin "17") (pinfunction "17_17") (pintype "passive"))
    )
    (net (code "143") (name "unconnected-(P1-Pad18)") (class "Default")
      (node (ref "P1") (pin "18") (pinfunction "18_18") (pintype "passive"))
    )
    (net (code "144") (name "unconnected-(P1-Pad21)") (class "Default")
      (node (ref "P1") (pin "21") (pinfunction "21_21") (pintype "passive"))
    )
    (net (code "145") (name "unconnected-(P1-Pad22)") (class "Default")
      (node (ref "P1") (pin "22") (pinfunction "22_22") (pintype "passive"))
    )
    (net (code "146") (name "unconnected-(P1-Pad23)") (class "Default")
      (node (ref "P1") (pin "23") (pinfunction "23_23") (pintype "passive"))
    )
    (net (code "147") (name "unconnected-(P1-Pad24)") (class "Default")
      (node (ref "P1") (pin "24") (pinfunction "24_24") (pintype "passive"))
    )
    (net (code "148") (name "unconnected-(P1-Pad27)") (class "Default")
      (node (ref "P1") (pin "27") (pinfunction "27_27") (pintype "passive"))
    )
    (net (code "149") (name "unconnected-(P1-Pad28)") (class "Default")
      (node (ref "P1") (pin "28") (pinfunction "28_28") (pintype "passive"))
    )
    (net (code "150") (name "unconnected-(P1-Pad29)") (class "Default")
      (node (ref "P1") (pin "29") (pinfunction "29_29") (pintype "passive"))
    )
    (net (code "151") (name "unconnected-(P1-Pad30)") (class "Default")
      (node (ref "P1") (pin "30") (pinfunction "30_30") (pintype "passive"))
    )
    (net (code "152") (name "unconnected-(P1-Pad33)") (class "Default")
      (node (ref "P1") (pin "33") (pinfunction "33_33") (pintype "passive"))
    )
    (net (code "153") (name "unconnected-(P1-Pad34)") (class "Default")
      (node (ref "P1") (pin "34") (pinfunction "34_34") (pintype "passive"))
    )
    (net (code "154") (name "unconnected-(P1-Pad35)") (class "Default")
      (node (ref "P1") (pin "35") (pinfunction "35_35") (pintype "passive"))
    )
    (net (code "155") (name "unconnected-(P1-Pad36)") (class "Default")
      (node (ref "P1") (pin "36") (pinfunction "36_36") (pintype "passive"))
    )
    (net (code "156") (name "unconnected-(P1-Pad39)") (class "Default")
      (node (ref "P1") (pin "39") (pinfunction "39_39") (pintype "passive"))
    )
    (net (code "157") (name "unconnected-(P1-Pad40)") (class "Default")
      (node (ref "P1") (pin "40") (pinfunction "40_40") (pintype "passive"))
    )
    (net (code "158") (name "unconnected-(P1-Pad41)") (class "Default")
      (node (ref "P1") (pin "41") (pinfunction "41_41") (pintype "passive"))
    )
    (net (code "159") (name "unconnected-(P1-Pad42)") (class "Default")
      (node (ref "P1") (pin "42") (pinfunction "42_42") (pintype "passive"))
    )
    (net (code "160") (name "unconnected-(P1-Pad45)") (class "Default")
      (node (ref "P1") (pin "45") (pinfunction "45_45") (pintype "passive"))
    )
    (net (code "161") (name "unconnected-(P1-Pad46)") (class "Default")
      (node (ref "P1") (pin "46") (pinfunction "46_46") (pintype "passive"))
    )
    (net (code "162") (name "unconnected-(P1-Pad47)") (class "Default")
      (node (ref "P1") (pin "47") (pinfunction "47_47") (pintype "passive"))
    )
    (net (code "163") (name "unconnected-(P1-Pad48)") (class "Default")
      (node (ref "P1") (pin "48") (pinfunction "48_48") (pintype "passive"))
    )
    (net (code "164") (name "unconnected-(P1-Pad51)") (class "Default")
      (node (ref "P1") (pin "51") (pinfunction "51_51") (pintype "passive"))
    )
    (net (code "165") (name "unconnected-(P1-Pad52)") (class "Default")
      (node (ref "P1") (pin "52") (pinfunction "52_52") (pintype "passive"))
    )
    (net (code "166") (name "unconnected-(P1-Pad53)") (class "Default")
      (node (ref "P1") (pin "53") (pinfunction "53_53") (pintype "passive"))
    )
    (net (code "167") (name "unconnected-(P1-Pad54)") (class "Default")
      (node (ref "P1") (pin "54") (pinfunction "54_54") (pintype "passive"))
    )
    (net (code "168") (name "unconnected-(P1-Pad57)") (class "Default")
      (node (ref "P1") (pin "57") (pinfunction "57_57") (pintype "passive"))
    )
    (net (code "169") (name "unconnected-(P1-Pad58)") (class "Default")
      (node (ref "P1") (pin "58") (pinfunction "58_58") (pintype "passive"))
    )
    (net (code "170") (name "unconnected-(P1-Pad59)") (class "Default")
      (node (ref "P1") (pin "59") (pinfunction "59_59") (pintype "passive"))
    )
    (net (code "171") (name "unconnected-(P1-Pad60)") (class "Default")
      (node (ref "P1") (pin "60") (pinfunction "60_60") (pintype "passive"))
    )
    (net (code "172") (name "unconnected-(P1-Pad63)") (class "Default")
      (node (ref "P1") (pin "63") (pinfunction "63_63") (pintype "passive"))
    )
    (net (code "173") (name "unconnected-(P1-Pad64)") (class "Default")
      (node (ref "P1") (pin "64") (pinfunction "64_64") (pintype "passive"))
    )
    (net (code "174") (name "unconnected-(P1-Pad65)") (class "Default")
      (node (ref "P1") (pin "65") (pinfunction "65_65") (pintype "passive"))
    )
    (net (code "175") (name "unconnected-(P1-Pad66)") (class "Default")
      (node (ref "P1") (pin "66") (pinfunction "66_66") (pintype "passive"))
    )
    (net (code "176") (name "unconnected-(P1-Pad69)") (class "Default")
      (node (ref "P1") (pin "69") (pinfunction "69_69") (pintype "passive"))
    )
    (net (code "177") (name "unconnected-(P1-Pad70)") (class "Default")
      (node (ref "P1") (pin "70") (pinfunction "70_70") (pintype "passive"))
    )
    (net (code "178") (name "unconnected-(P1-Pad71)") (class "Default")
      (node (ref "P1") (pin "71") (pinfunction "71_71") (pintype "passive"))
    )
    (net (code "179") (name "unconnected-(P1-Pad72)") (class "Default")
      (node (ref "P1") (pin "72") (pinfunction "72_72") (pintype "passive"))
    )
    (net (code "180") (name "unconnected-(P1-Pad75)") (class "Default")
      (node (ref "P1") (pin "75") (pinfunction "75_75") (pintype "passive"))
    )
    (net (code "181") (name "unconnected-(P1-Pad76)") (class "Default")
      (node (ref "P1") (pin "76") (pinfunction "76_76") (pintype "passive"))
    )
    (net (code "182") (name "unconnected-(P1-Pad77)") (class "Default")
      (node (ref "P1") (pin "77") (pinfunction "77_77") (pintype "passive"))
    )
    (net (code "183") (name "unconnected-(P1-Pad78)") (class "Default")
      (node (ref "P1") (pin "78") (pinfunction "78_78") (pintype "passive"))
    )
    (net (code "184") (name "unconnected-(P1-Pad81)") (class "Default")
      (node (ref "P1") (pin "81") (pinfunction "81_81") (pintype "passive"))
    )
    (net (code "185") (name "unconnected-(P1-Pad82)") (class "Default")
      (node (ref "P1") (pin "82") (pinfunction "82_82") (pintype "passive"))
    )
    (net (code "186") (name "unconnected-(P1-Pad83)") (class "Default")
      (node (ref "P1") (pin "83") (pinfunction "83_83") (pintype "passive"))
    )
    (net (code "187") (name "unconnected-(P1-Pad84)") (class "Default")
      (node (ref "P1") (pin "84") (pinfunction "84_84") (pintype "passive"))
    )
    (net (code "188") (name "unconnected-(P1-Pad87)") (class "Default")
      (node (ref "P1") (pin "87") (pinfunction "87_87") (pintype "passive"))
    )
    (net (code "189") (name "unconnected-(P1-Pad88)") (class "Default")
      (node (ref "P1") (pin "88") (pinfunction "88_88") (pintype "passive"))
    )
    (net (code "190") (name "unconnected-(P1-Pad89)") (class "Default")
      (node (ref "P1") (pin "89") (pinfunction "89_89") (pintype "passive"))
    )
    (net (code "191") (name "unconnected-(P1-Pad90)") (class "Default")
      (node (ref "P1") (pin "90") (pinfunction "90_90") (pintype "passive"))
    )
    (net (code "192") (name "unconnected-(P1-Pad93)") (class "Default")
      (node (ref "P1") (pin "93") (pinfunction "93_93") (pintype "passive"))
    )
    (net (code "193") (name "unconnected-(P1-Pad94)") (class "Default")
      (node (ref "P1") (pin "94") (pinfunction "94_94") (pintype "passive"))
    )
    (net (code "194") (name "unconnected-(P1-Pad95)") (class "Default")
      (node (ref "P1") (pin "95") (pinfunction "95_95") (pintype "passive"))
    )
    (net (code "195") (name "unconnected-(P1-Pad96)") (class "Default")
      (node (ref "P1") (pin "96") (pinfunction "96_96") (pintype "passive"))
    )
    (net (code "196") (name "unconnected-(P1-Pad99)") (class "Default")
      (node (ref "P1") (pin "99") (pinfunction "99_99") (pintype "passive"))
    )
    (net (code "197") (name "unconnected-(P1-Pad100)") (class "Default")
      (node (ref "P1") (pin "100") (pinfunction "100_100") (pintype "passive"))
    )
    (net (code "198") (name "unconnected-(P1-Pad101)") (class "Default")
      (node (ref "P1") (pin "101") (pinfunction "101_101") (pintype "passive"))
    )
    (net (code "199") (name "unconnected-(P1-Pad102)") (class "Default")
      (node (ref "P1") (pin "102") (pinfunction "102_102") (pintype "passive"))
    )
    (net (code "200") (name "unconnected-(P1-Pad105)") (class "Default")
      (node (ref "P1") (pin "105") (pinfunction "105_105") (pintype "passive"))
    )
    (net (code "201") (name "unconnected-(P1-Pad106)") (class "Default")
      (node (ref "P1") (pin "106") (pinfunction "106_106") (pintype "passive"))
    )
    (net (code "202") (name "unconnected-(P1-Pad107)") (class "Default")
      (node (ref "P1") (pin "107") (pinfunction "107_107") (pintype "passive"))
    )
    (net (code "203") (name "unconnected-(P1-Pad108)") (class "Default")
      (node (ref "P1") (pin "108") (pinfunction "108_108") (pintype "passive"))
    )
    (net (code "204") (name "unconnected-(P1-Pad111)") (class "Default")
      (node (ref "P1") (pin "111") (pinfunction "111_111") (pintype "passive"))
    )
    (net (code "205") (name "unconnected-(P1-Pad112)") (class "Default")
      (node (ref "P1") (pin "112") (pinfunction "112_112") (pintype "passive"))
    )
    (net (code "206") (name "unconnected-(P1-Pad113)") (class "Default")
      (node (ref "P1") (pin "113") (pinfunction "113_113") (pintype "passive"))
    )
    (net (code "207") (name "unconnected-(P1-Pad114)") (class "Default")
      (node (ref "P1") (pin "114") (pinfunction "114_114") (pintype "passive"))
    )
    (net (code "208") (name "unconnected-(P1-Pad117)") (class "Default")
      (node (ref "P1") (pin "117") (pinfunction "117_117") (pintype "passive"))
    )
    (net (code "209") (name "unconnected-(P1-Pad118)") (class "Default")
      (node (ref "P1") (pin "118") (pinfunction "118_118") (pintype "passive"))
    )
    (net (code "210") (name "unconnected-(P1-Pad119)") (class "Default")
      (node (ref "P1") (pin "119") (pinfunction "119_119") (pintype "passive"))
    )
    (net (code "211") (name "unconnected-(P1-Pad120)") (class "Default")
      (node (ref "P1") (pin "120") (pinfunction "120_120") (pintype "passive"))
    )
    (net (code "212") (name "unconnected-(P1-Pad123)") (class "Default")
      (node (ref "P1") (pin "123") (pinfunction "123_123") (pintype "passive"))
    )
    (net (code "213") (name "unconnected-(P1-Pad124)") (class "Default")
      (node (ref "P1") (pin "124") (pinfunction "124_124") (pintype "passive"))
    )
    (net (code "214") (name "unconnected-(P1-Pad125)") (class "Default")
      (node (ref "P1") (pin "125") (pinfunction "125_125") (pintype "passive"))
    )
    (net (code "215") (name "unconnected-(P1-Pad126)") (class "Default")
      (node (ref "P1") (pin "126") (pinfunction "126_126") (pintype "passive"))
    )
    (net (code "216") (name "unconnected-(P1-Pad128)") (class "Default")
      (node (ref "P1") (pin "128") (pinfunction "128_128") (pintype "passive"))
    )
    (net (code "217") (name "unconnected-(P1-Pad129)") (class "Default")
      (node (ref "P1") (pin "129") (pinfunction "129_129") (pintype "passive"))
    )
    (net (code "218") (name "unconnected-(P1-Pad130)") (class "Default")
      (node (ref "P1") (pin "130") (pinfunction "130_130") (pintype "passive"))
    )
    (net (code "219") (name "unconnected-(P1-Pad131)") (class "Default")
      (node (ref "P1") (pin "131") (pinfunction "131_131") (pintype "passive"))
    )
    (net (code "220") (name "unconnected-(P1-Pad132)") (class "Default")
      (node (ref "P1") (pin "132") (pinfunction "132_132") (pintype "passive"))
    )
    (net (code "221") (name "unconnected-(P1-Pad135)") (class "Default")
      (node (ref "P1") (pin "135") (pinfunction "135_135") (pintype "passive"))
    )
    (net (code "222") (name "unconnected-(P1-Pad136)") (class "Default")
      (node (ref "P1") (pin "136") (pinfunction "136_136") (pintype "passive"))
    )
    (net (code "223") (name "unconnected-(P1-Pad137)") (class "Default")
      (node (ref "P1") (pin "137") (pinfunction "137_137") (pintype "passive"))
    )
    (net (code "224") (name "unconnected-(P1-Pad138)") (class "Default")
      (node (ref "P1") (pin "138") (pinfunction "138_138") (pintype "passive"))
    )
    (net (code "225") (name "unconnected-(P1-Pad141)") (class "Default")
      (node (ref "P1") (pin "141") (pinfunction "141_141") (pintype "passive"))
    )
    (net (code "226") (name "unconnected-(P1-Pad142)") (class "Default")
      (node (ref "P1") (pin "142") (pinfunction "142_142") (pintype "passive"))
    )
    (net (code "227") (name "unconnected-(P1-Pad143)") (class "Default")
      (node (ref "P1") (pin "143") (pinfunction "143_143") (pintype "passive"))
    )
    (net (code "228") (name "unconnected-(P1-Pad144)") (class "Default")
      (node (ref "P1") (pin "144") (pinfunction "144_144") (pintype "passive"))
    )
    (net (code "229") (name "unconnected-(P1-Pad147)") (class "Default")
      (node (ref "P1") (pin "147") (pinfunction "147_147") (pintype "passive"))
    )
    (net (code "230") (name "unconnected-(P1-Pad148)") (class "Default")
      (node (ref "P1") (pin "148") (pinfunction "148_148") (pintype "passive"))
    )
    (net (code "231") (name "unconnected-(P1-Pad149)") (class "Default")
      (node (ref "P1") (pin "149") (pinfunction "149_149") (pintype "passive"))
    )
    (net (code "232") (name "unconnected-(P1-Pad150)") (class "Default")
      (node (ref "P1") (pin "150") (pinfunction "150_150") (pintype "passive"))
    )
    (net (code "233") (name "unconnected-(P1-Pad153)") (class "Default")
      (node (ref "P1") (pin "153") (pinfunction "153_153") (pintype "passive"))
    )
    (net (code "234") (name "unconnected-(P1-Pad154)") (class "Default")
      (node (ref "P1") (pin "154") (pinfunction "154_154") (pintype "passive"))
    )
    (net (code "235") (name "unconnected-(P1-Pad155)") (class "Default")
      (node (ref "P1") (pin "155") (pinfunction "155_155") (pintype "passive"))
    )
    (net (code "236") (name "unconnected-(P1-Pad156)") (class "Default")
      (node (ref "P1") (pin "156") (pinfunction "156_156") (pintype "passive"))
    )
    (net (code "237") (name "unconnected-(P1-Pad158)") (class "Default")
      (node (ref "P1") (pin "158") (pinfunction "158_158") (pintype "passive"))
    )
    (net (code "238") (name "unconnected-(P1-Pad159)") (class "Default")
      (node (ref "P1") (pin "159") (pinfunction "159_159") (pintype "passive"))
    )
    (net (code "239") (name "unconnected-(P1-Pad160)") (class "Default")
      (node (ref "P1") (pin "160") (pinfunction "160_160") (pintype "passive"))
    )
    (net (code "240") (name "unconnected-(P1-Pad161)") (class "Default")
      (node (ref "P1") (pin "161") (pinfunction "161_161") (pintype "passive"))
    )
    (net (code "241") (name "unconnected-(P1-Pad162)") (class "Default")
      (node (ref "P1") (pin "162") (pinfunction "162_162") (pintype "passive"))
    )
    (net (code "242") (name "unconnected-(P1-Pad165)") (class "Default")
      (node (ref "P1") (pin "165") (pinfunction "165_165") (pintype "passive"))
    )
    (net (code "243") (name "unconnected-(P1-Pad166)") (class "Default")
      (node (ref "P1") (pin "166") (pinfunction "166_166") (pintype "passive"))
    )
    (net (code "244") (name "unconnected-(P1-Pad167)") (class "Default")
      (node (ref "P1") (pin "167") (pinfunction "167_167") (pintype "passive"))
    )
    (net (code "245") (name "unconnected-(P1-Pad171)") (class "Default")
      (node (ref "P1") (pin "171") (pinfunction "171_171") (pintype "passive"))
    )
    (net (code "246") (name "unconnected-(P1-Pad172)") (class "Default")
      (node (ref "P1") (pin "172") (pinfunction "172_172") (pintype "passive"))
    )
    (net (code "247") (name "unconnected-(P1-Pad173)") (class "Default")
      (node (ref "P1") (pin "173") (pinfunction "173_173") (pintype "passive"))
    )
    (net (code "248") (name "unconnected-(P1-Pad174)") (class "Default")
      (node (ref "P1") (pin "174") (pinfunction "174_174") (pintype "passive"))
    )
    (net (code "249") (name "unconnected-(P1-Pad175)") (class "Default")
      (node (ref "P1") (pin "175") (pinfunction "175_175") (pintype "passive"))
    )
    (net (code "250") (name "unconnected-(P1-Pad176)") (class "Default")
      (node (ref "P1") (pin "176") (pinfunction "176_176") (pintype "passive"))
    )
    (net (code "251") (name "unconnected-(P1-Pad178)") (class "Default")
      (node (ref "P1") (pin "178") (pinfunction "178_178") (pintype "passive"))
    )
    (net (code "252") (name "unconnected-(P1-Pad179)") (class "Default")
      (node (ref "P1") (pin "179") (pinfunction "179_179") (pintype "passive"))
    )
    (net (code "253") (name "unconnected-(P1-Pad180)") (class "Default")
      (node (ref "P1") (pin "180") (pinfunction "180_180") (pintype "passive"))
    )
    (net (code "254") (name "unconnected-(P1-Pad183)") (class "Default")
      (node (ref "P1") (pin "183") (pinfunction "183_183") (pintype "passive"))
    )
    (net (code "255") (name "unconnected-(P1-Pad184)") (class "Default")
      (node (ref "P1") (pin "184") (pinfunction "184_184") (pintype "passive"))
    )
    (net (code "256") (name "unconnected-(P1-Pad185)") (class "Default")
      (node (ref "P1") (pin "185") (pinfunction "185_185") (pintype "passive"))
    )
    (net (code "257") (name "unconnected-(P1-Pad186)") (class "Default")
      (node (ref "P1") (pin "186") (pinfunction "186_186") (pintype "passive"))
    )
    (net (code "258") (name "unconnected-(P1-Pad189)") (class "Default")
      (node (ref "P1") (pin "189") (pinfunction "189_189") (pintype "passive"))
    )
    (net (code "259") (name "unconnected-(P1-Pad190)") (class "Default")
      (node (ref "P1") (pin "190") (pinfunction "190_190") (pintype "passive"))
    )
  )
)
